# Schematic.net
KiCad netlist of a schematic drawn in Altium Designer
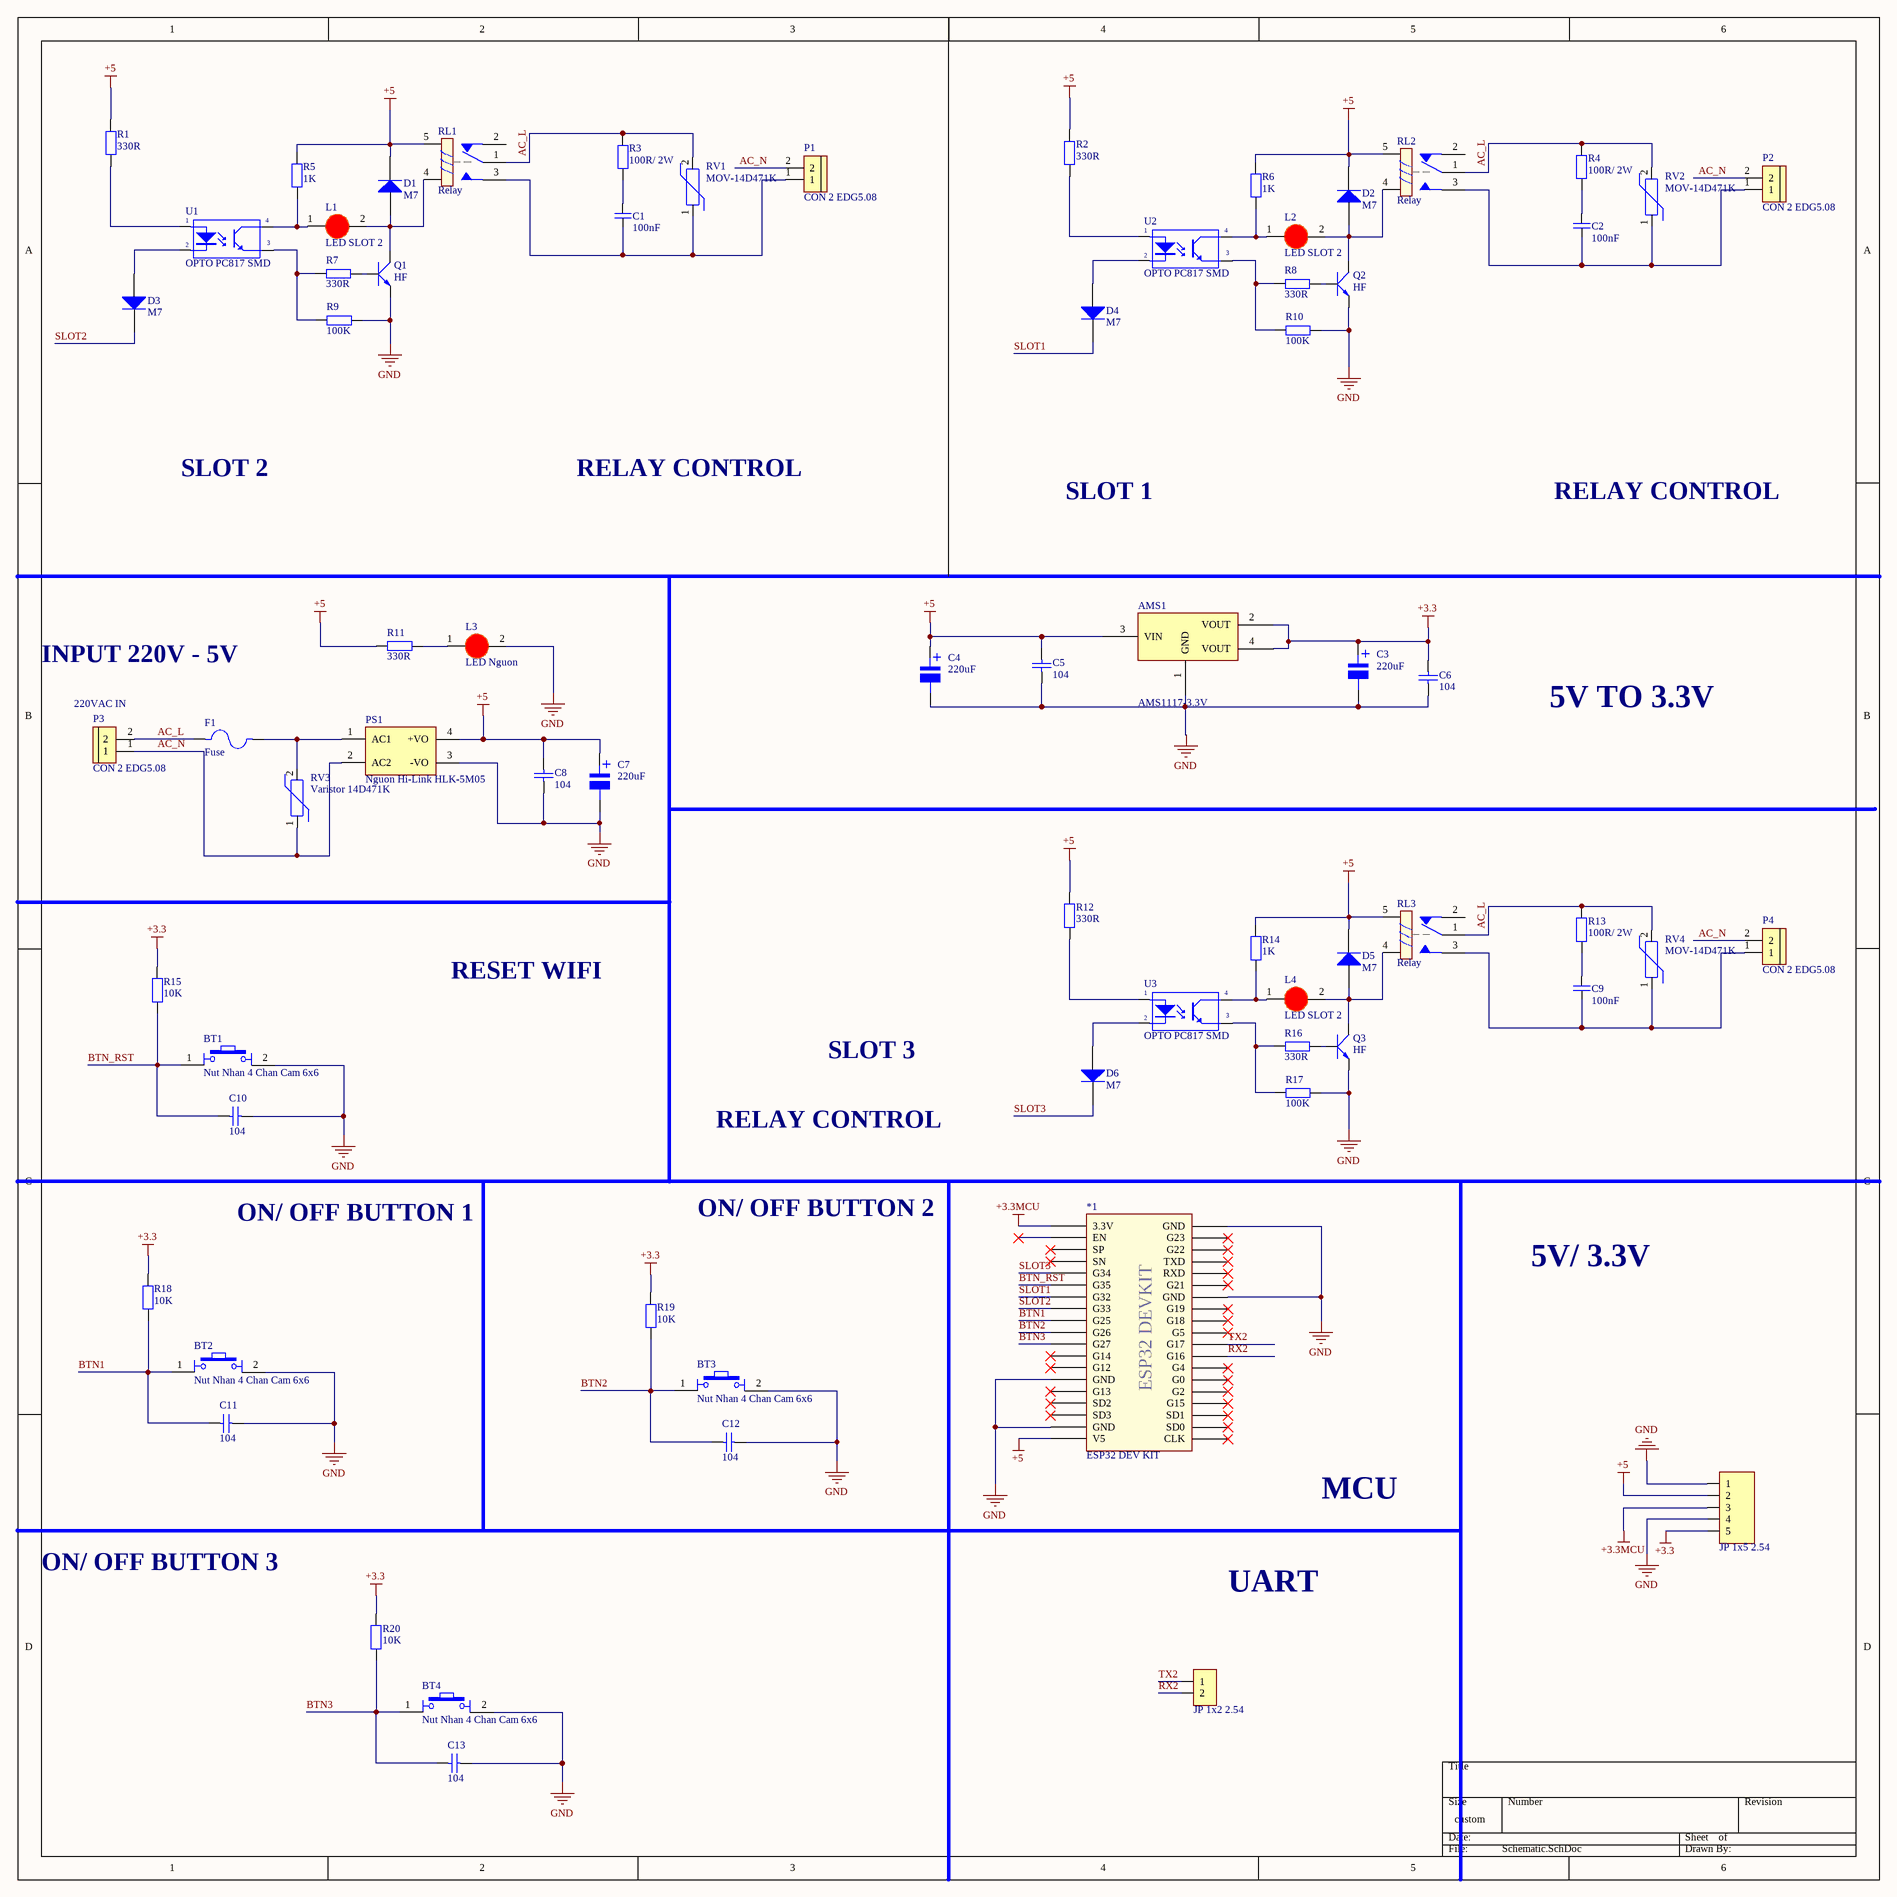
[diagram p0: Schematic.SchDoc]

(export (version "E")
  (design (tool "Eeschema 10.0.6"))
  (components
    (comp (ref "*1")
      (value "ESP32 DEV KIT")
      (footprint "ESP32 DEVKIT")
      (libsource (lib "Altium_Lib_by_KhueNguyenCreator") (part "ESP32 DEV KIT"))
    )
    (comp (ref "AMS1")
      (value "AMS1117-3.3V")
      (footprint "SOT223")
      (description "Dán")
      (libsource (lib "Altium_Lib_by_KhueNguyenCreator") (part "AMS1117 SMD"))
    )
    (comp (ref "BT1")
      (value "Nut Nhan 4 Chan Cam 6x6")
      (footprint "Nut Nhan 4 Chan Cam 6x6")
      (description "Nut Nhan 4 Chan 6x6mm")
      (libsource (lib "Altium_Lib_by_KhueNguyenCreator") (part "Nut Nhan 4 Chan Cam 6x6"))
    )
    (comp (ref "BT2")
      (value "Nut Nhan 4 Chan Cam 6x6")
      (footprint "Nut Nhan 4 Chan Cam 6x6")
      (description "Nut Nhan 4 Chan 6x6mm")
      (libsource (lib "Altium_Lib_by_KhueNguyenCreator") (part "Nut Nhan 4 Chan Cam 6x6"))
    )
    (comp (ref "BT3")
      (value "Nut Nhan 4 Chan Cam 6x6")
      (footprint "Nut Nhan 4 Chan Cam 6x6")
      (description "Nut Nhan 4 Chan 6x6mm")
      (libsource (lib "Altium_Lib_by_KhueNguyenCreator") (part "Nut Nhan 4 Chan Cam 6x6"))
    )
    (comp (ref "BT4")
      (value "Nut Nhan 4 Chan Cam 6x6")
      (footprint "Nut Nhan 4 Chan Cam 6x6")
      (description "Nut Nhan 4 Chan 6x6mm")
      (libsource (lib "Altium_Lib_by_KhueNguyenCreator") (part "Nut Nhan 4 Chan Cam 6x6"))
    )
    (comp (ref "C1")
      (value "100nF")
      (footprint "Cap_Poly_684J400V")
      (libsource (lib "Electronic4u") (part "Cap_Non-Polar"))
    )
    (comp (ref "C2")
      (value "100nF")
      (footprint "Cap_Poly_684J400V")
      (libsource (lib "Electronic4u") (part "Cap_Non-Polar"))
    )
    (comp (ref "C3")
      (value "220uF")
      (footprint "tu nhom 6.3 (d)")
      (description "Dán")
      (libsource (lib "Altium_Lib_by_KhueNguyenCreator") (part "Tu Nhom 220uF 16V"))
    )
    (comp (ref "C4")
      (value "220uF")
      (footprint "tu nhom 6.3 (d)")
      (description "Dán")
      (libsource (lib "Altium_Lib_by_KhueNguyenCreator") (part "Tu Nhom 220uF 16V"))
    )
    (comp (ref "C5")
      (value "104")
      (footprint "tu 0805")
      (description "Dán")
      (libsource (lib "Altium_Lib_by_KhueNguyenCreator") (part "Tu 0805 104 50V 10%"))
    )
    (comp (ref "C6")
      (value "104")
      (footprint "tu 0805")
      (description "Dán")
      (libsource (lib "Altium_Lib_by_KhueNguyenCreator") (part "Tu 0805 104 50V 10%"))
    )
    (comp (ref "C7")
      (value "220uF")
      (footprint "tu nhom 6.3 (d)")
      (description "Dán")
      (libsource (lib "Altium_Lib_by_KhueNguyenCreator") (part "Tu Nhom 220uF 16V"))
    )
    (comp (ref "C8")
      (value "104")
      (footprint "tu 0805")
      (description "Dán")
      (libsource (lib "Altium_Lib_by_KhueNguyenCreator") (part "Tu 0805 104 50V 10%"))
    )
    (comp (ref "C9")
      (value "100nF")
      (footprint "Cap_Poly_684J400V")
      (libsource (lib "Electronic4u") (part "Cap_Non-Polar"))
    )
    (comp (ref "C10")
      (value "104")
      (footprint "tu 0805")
      (description "Dán")
      (libsource (lib "Altium_Lib_by_KhueNguyenCreator") (part "Tu 0805 104 50V 10%"))
    )
    (comp (ref "C11")
      (value "104")
      (footprint "tu 0805")
      (description "Dán")
      (libsource (lib "Altium_Lib_by_KhueNguyenCreator") (part "Tu 0805 104 50V 10%"))
    )
    (comp (ref "C12")
      (value "104")
      (footprint "tu 0805")
      (description "Dán")
      (libsource (lib "Altium_Lib_by_KhueNguyenCreator") (part "Tu 0805 104 50V 10%"))
    )
    (comp (ref "C13")
      (value "104")
      (footprint "tu 0805")
      (description "Dán")
      (libsource (lib "Altium_Lib_by_KhueNguyenCreator") (part "Tu 0805 104 50V 10%"))
    )
    (comp (ref "D1")
      (value "M7")
      (footprint "DIODE SMA")
      (description "Dán")
      (libsource (lib "Altium_Lib_by_KhueNguyenCreator") (part "Diode M7 ( 4007 )"))
    )
    (comp (ref "D2")
      (value "M7")
      (footprint "DIODE SMA")
      (description "Dán")
      (libsource (lib "Altium_Lib_by_KhueNguyenCreator") (part "Diode M7 ( 4007 )"))
    )
    (comp (ref "D3")
      (value "M7")
      (footprint "DIODE SMA")
      (description "Dán")
      (libsource (lib "Altium_Lib_by_KhueNguyenCreator") (part "Diode M7 ( 4007 )"))
    )
    (comp (ref "D4")
      (value "M7")
      (footprint "DIODE SMA")
      (description "Dán")
      (libsource (lib "Altium_Lib_by_KhueNguyenCreator") (part "Diode M7 ( 4007 )"))
    )
    (comp (ref "D5")
      (value "M7")
      (footprint "DIODE SMA")
      (description "Dán")
      (libsource (lib "Altium_Lib_by_KhueNguyenCreator") (part "Diode M7 ( 4007 )"))
    )
    (comp (ref "D6")
      (value "M7")
      (footprint "DIODE SMA")
      (description "Dán")
      (libsource (lib "Altium_Lib_by_KhueNguyenCreator") (part "Diode M7 ( 4007 )"))
    )
    (comp (ref "F1")
      (value "Fuse")
      (footprint "FUSE")
      (description "Fuse, TE5 369 Series, Through Hole, Slow Blow, 300VAC, 1A, Radial ¦ Littelfuse 36911000000")
      (fields (field (name "MF") "Littelfuse") (field (name "MP") "36911000000"))
      (libsource (lib "Altium_Lib_by_KhueNguyenCreator") (part "Fuse"))
    )
    (comp (ref "JP1")
      (value "JP 1x5 2.54")
      (footprint "JP 1x5 DT")
      (description "Cắm")
      (libsource (lib "Altium_Lib_by_KhueNguyenCreator") (part "JP 1x5 2.54 Duc Thang"))
    )
    (comp (ref "JP2")
      (value "JP 1x2 2.54")
      (footprint "JP 1x2 DT")
      (description "Cắm")
      (libsource (lib "Altium_Lib_by_KhueNguyenCreator") (part "JP 1x2 2.54 Duc Thang"))
    )
    (comp (ref "L1")
      (value "LED SLOT 2")
      (footprint "LED-5MM-RED")
      (description "Cắm")
      (libsource (lib "Altium_Lib_by_KhueNguyenCreator") (part "LED 5mm Do"))
    )
    (comp (ref "L2")
      (value "LED SLOT 2")
      (footprint "LED-5MM-RED")
      (description "Cắm")
      (libsource (lib "Altium_Lib_by_KhueNguyenCreator") (part "LED 5mm Do"))
    )
    (comp (ref "L3")
      (value "LED Nguon")
      (footprint "LED-5MM-RED")
      (description "Cắm")
      (libsource (lib "Altium_Lib_by_KhueNguyenCreator") (part "LED 5mm Do"))
    )
    (comp (ref "L4")
      (value "LED SLOT 2")
      (footprint "LED-5MM-RED")
      (description "Cắm")
      (libsource (lib "Altium_Lib_by_KhueNguyenCreator") (part "LED 5mm Do"))
    )
    (comp (ref "P1")
      (value "CON 2 EDG5.08")
      (footprint "CON 2 2EDG5.08")
      (description "Cắm")
      (libsource (lib "Altium_Lib_by_KhueNguyenCreator") (part "CON 2 EDG5.08"))
    )
    (comp (ref "P2")
      (value "CON 2 EDG5.08")
      (footprint "CON 2 2EDG5.08")
      (description "Cắm")
      (libsource (lib "Altium_Lib_by_KhueNguyenCreator") (part "CON 2 EDG5.08"))
    )
    (comp (ref "P3")
      (value "CON 2 EDG5.08")
      (footprint "CON 2 2EDG5.08")
      (description "Cắm")
      (libsource (lib "") (part "CON 2 EDG5.08_1"))
    )
    (comp (ref "P4")
      (value "CON 2 EDG5.08")
      (footprint "CON 2 2EDG5.08")
      (description "Cắm")
      (libsource (lib "Altium_Lib_by_KhueNguyenCreator") (part "CON 2 EDG5.08"))
    )
    (comp (ref "PS1")
      (value "Nguon Hi-Link HLK-5M05")
      (footprint "Nguon HI-LINK 5M05")
      (description "AC DC 220V to 5V 5W 5Watt Isolated Switching Step-Down Power Supply Module Converter")
      (fields (field (name "MF") "Hi-link") (field (name "MP") "HLK-5M05"))
      (libsource (lib "Altium_Lib_by_KhueNguyenCreator") (part "Nguon Hi-Link HLK-5M05"))
    )
    (comp (ref "Q1")
      (value "HF")
      (footprint "SOT-23")
      (description "SOT-23")
      (libsource (lib "Altium_Lib_by_KhueNguyenCreator") (part "Trans C1815 HF SMD"))
    )
    (comp (ref "Q2")
      (value "HF")
      (footprint "SOT-23")
      (description "SOT-23")
      (libsource (lib "Altium_Lib_by_KhueNguyenCreator") (part "Trans C1815 HF SMD"))
    )
    (comp (ref "Q3")
      (value "HF")
      (footprint "SOT-23")
      (description "SOT-23")
      (libsource (lib "Altium_Lib_by_KhueNguyenCreator") (part "Trans C1815 HF SMD"))
    )
    (comp (ref "R1")
      (value "330R")
      (footprint "Tro SMD 0805")
      (description "Dán")
      (libsource (lib "Altium_Lib_by_KhueNguyenCreator") (part "Tro 0805 5% 330R"))
    )
    (comp (ref "R2")
      (value "330R")
      (footprint "Tro SMD 0805")
      (description "Dán")
      (libsource (lib "Altium_Lib_by_KhueNguyenCreator") (part "Tro 0805 5% 330R"))
    )
    (comp (ref "R3")
      (value "100R/ 2W")
      (footprint "tro vach 2w")
      (description "Cắm")
      (libsource (lib "Altium_Lib_by_KhueNguyenCreator") (part "Tro Vach 2W 5% 100R"))
    )
    (comp (ref "R4")
      (value "100R/ 2W")
      (footprint "tro vach 2w")
      (description "Cắm")
      (libsource (lib "Altium_Lib_by_KhueNguyenCreator") (part "Tro Vach 2W 5% 100R"))
    )
    (comp (ref "R5")
      (value "1K")
      (footprint "Tro SMD 0805")
      (description "Dán")
      (libsource (lib "Altium_Lib_by_KhueNguyenCreator") (part "Tro 0805 5% 330R"))
    )
    (comp (ref "R6")
      (value "1K")
      (footprint "Tro SMD 0805")
      (description "Dán")
      (libsource (lib "Altium_Lib_by_KhueNguyenCreator") (part "Tro 0805 5% 330R"))
    )
    (comp (ref "R7")
      (value "330R")
      (footprint "Tro SMD 0805")
      (description "Dán")
      (libsource (lib "Altium_Lib_by_KhueNguyenCreator") (part "Tro 0805 5% 330R"))
    )
    (comp (ref "R8")
      (value "330R")
      (footprint "Tro SMD 0805")
      (description "Dán")
      (libsource (lib "Altium_Lib_by_KhueNguyenCreator") (part "Tro 0805 5% 330R"))
    )
    (comp (ref "R9")
      (value "100K")
      (footprint "Tro SMD 0805")
      (description "Dán")
      (libsource (lib "Altium_Lib_by_KhueNguyenCreator") (part "Tro 0805 5% 330R"))
    )
    (comp (ref "R10")
      (value "100K")
      (footprint "Tro SMD 0805")
      (description "Dán")
      (libsource (lib "Altium_Lib_by_KhueNguyenCreator") (part "Tro 0805 5% 330R"))
    )
    (comp (ref "R11")
      (value "330R")
      (footprint "Tro SMD 0805")
      (description "Dán")
      (libsource (lib "Altium_Lib_by_KhueNguyenCreator") (part "Tro 0805 5% 330R"))
    )
    (comp (ref "R12")
      (value "330R")
      (footprint "Tro SMD 0805")
      (description "Dán")
      (libsource (lib "Altium_Lib_by_KhueNguyenCreator") (part "Tro 0805 5% 330R"))
    )
    (comp (ref "R13")
      (value "100R/ 2W")
      (footprint "tro vach 2w")
      (description "Cắm")
      (libsource (lib "Altium_Lib_by_KhueNguyenCreator") (part "Tro Vach 2W 5% 100R"))
    )
    (comp (ref "R14")
      (value "1K")
      (footprint "Tro SMD 0805")
      (description "Dán")
      (libsource (lib "Altium_Lib_by_KhueNguyenCreator") (part "Tro 0805 5% 330R"))
    )
    (comp (ref "R15")
      (value "10K")
      (footprint "Tro SMD 0805")
      (description "Dán")
      (libsource (lib "Altium_Lib_by_KhueNguyenCreator") (part "Tro 0805 5% 330R"))
    )
    (comp (ref "R16")
      (value "330R")
      (footprint "Tro SMD 0805")
      (description "Dán")
      (libsource (lib "Altium_Lib_by_KhueNguyenCreator") (part "Tro 0805 5% 330R"))
    )
    (comp (ref "R17")
      (value "100K")
      (footprint "Tro SMD 0805")
      (description "Dán")
      (libsource (lib "Altium_Lib_by_KhueNguyenCreator") (part "Tro 0805 5% 330R"))
    )
    (comp (ref "R18")
      (value "10K")
      (footprint "Tro SMD 0805")
      (description "Dán")
      (libsource (lib "Altium_Lib_by_KhueNguyenCreator") (part "Tro 0805 5% 330R"))
    )
    (comp (ref "R19")
      (value "10K")
      (footprint "Tro SMD 0805")
      (description "Dán")
      (libsource (lib "Altium_Lib_by_KhueNguyenCreator") (part "Tro 0805 5% 330R"))
    )
    (comp (ref "R20")
      (value "10K")
      (footprint "Tro SMD 0805")
      (description "Dán")
      (libsource (lib "Altium_Lib_by_KhueNguyenCreator") (part "Tro 0805 5% 330R"))
    )
    (comp (ref "RL1")
      (value "Relay")
      (footprint "Relay 5 Chan SRD")
      (description "Relay 5 Chan")
      (libsource (lib "Altium_Lib_by_KhueNguyenCreator") (part "Relay 5 Chan SRD"))
    )
    (comp (ref "RL2")
      (value "Relay")
      (footprint "Relay 5 Chan SRD")
      (description "Relay 5 Chan")
      (libsource (lib "Altium_Lib_by_KhueNguyenCreator") (part "Relay 5 Chan SRD"))
    )
    (comp (ref "RL3")
      (value "Relay")
      (footprint "Relay 5 Chan SRD")
      (description "Relay 5 Chan")
      (libsource (lib "Altium_Lib_by_KhueNguyenCreator") (part "Relay 5 Chan SRD"))
    )
    (comp (ref "RV1")
      (value "MOV-14D471K")
      (footprint "MOV14D471K")
      (description "470 V 4.5 kA Varistor 1 Circuit Through Hole Disc 14mm")
      (fields (field (name "MF") "Bourns"))
      (libsource (lib "Altium_Lib_by_KhueNguyenCreator") (part "MOV-14D471K"))
    )
    (comp (ref "RV2")
      (value "MOV-14D471K")
      (footprint "MOV14D471K")
      (description "470 V 4.5 kA Varistor 1 Circuit Through Hole Disc 14mm")
      (fields (field (name "MF") "Bourns"))
      (libsource (lib "Altium_Lib_by_KhueNguyenCreator") (part "MOV-14D471K"))
    )
    (comp (ref "RV3")
      (value "Varistor 14D471K")
      (footprint "MOV14D471K")
      (description "470 V 4.5 kA Varistor 1 Circuit Through Hole Disc 14mm")
      (fields (field (name "MP") "MOV-14D471K") (field (name "MF") "Bourns"))
      (libsource (lib "MOV-14D471K") (part "MOV-14D471K"))
    )
    (comp (ref "RV4")
      (value "MOV-14D471K")
      (footprint "MOV14D471K")
      (description "470 V 4.5 kA Varistor 1 Circuit Through Hole Disc 14mm")
      (fields (field (name "MF") "Bourns"))
      (libsource (lib "Altium_Lib_by_KhueNguyenCreator") (part "MOV-14D471K"))
    )
    (comp (ref "U1")
      (value "OPTO PC817 SMD")
      (footprint "SOP4")
      (description "Single Opto")
      (libsource (lib "Altium_Lib_by_KhueNguyenCreator") (part "OPTO PC817 SMD"))
    )
    (comp (ref "U2")
      (value "OPTO PC817 SMD")
      (footprint "SOP4")
      (description "Single Opto")
      (libsource (lib "Altium_Lib_by_KhueNguyenCreator") (part "OPTO PC817 SMD"))
    )
    (comp (ref "U3")
      (value "OPTO PC817 SMD")
      (footprint "SOP4")
      (description "Single Opto")
      (libsource (lib "Altium_Lib_by_KhueNguyenCreator") (part "OPTO PC817 SMD"))
    )
  )
  (nets
    (net (code "1") (name "+3.3") (class "Default")
      (node (ref "AMS1") (pin "2") (pinfunction "VOUT_2") (pintype "passive"))
      (node (ref "AMS1") (pin "4") (pinfunction "VOUT_4") (pintype "passive"))
      (node (ref "C3") (pin "1") (pinfunction "1_1") (pintype "passive"))
      (node (ref "C6") (pin "1") (pinfunction "1_1") (pintype "passive"))
      (node (ref "JP1") (pin "5") (pinfunction "5_5") (pintype "passive"))
      (node (ref "R15") (pin "1") (pinfunction "1_1") (pintype "passive"))
      (node (ref "R18") (pin "1") (pinfunction "1_1") (pintype "passive"))
      (node (ref "R19") (pin "1") (pinfunction "1_1") (pintype "passive"))
      (node (ref "R20") (pin "1") (pinfunction "1_1") (pintype "passive"))
    )
    (net (code "2") (name "+3.3MCU") (class "Default")
      (node (ref "*1") (pin "1") (pinfunction "3.3V_1") (pintype "passive"))
      (node (ref "JP1") (pin "3") (pinfunction "3_3") (pintype "passive"))
    )
    (net (code "3") (name "+5") (class "Default")
      (node (ref "*1") (pin "19") (pinfunction "V5_19") (pintype "passive"))
      (node (ref "AMS1") (pin "3") (pinfunction "VIN_3") (pintype "passive"))
      (node (ref "C4") (pin "1") (pinfunction "1_1") (pintype "passive"))
      (node (ref "C5") (pin "1") (pinfunction "1_1") (pintype "passive"))
      (node (ref "C7") (pin "1") (pinfunction "1_1") (pintype "passive"))
      (node (ref "C8") (pin "1") (pinfunction "1_1") (pintype "passive"))
      (node (ref "D1") (pin "2") (pinfunction "K_2") (pintype "passive"))
      (node (ref "D2") (pin "2") (pinfunction "K_2") (pintype "passive"))
      (node (ref "D5") (pin "2") (pinfunction "K_2") (pintype "passive"))
      (node (ref "JP1") (pin "2") (pinfunction "2_2") (pintype "passive"))
      (node (ref "PS1") (pin "4") (pinfunction "+VO_4") (pintype "passive"))
      (node (ref "R1") (pin "2") (pinfunction "2_2") (pintype "passive"))
      (node (ref "R11") (pin "2") (pinfunction "2_2") (pintype "passive"))
      (node (ref "R12") (pin "2") (pinfunction "2_2") (pintype "passive"))
      (node (ref "R14") (pin "2") (pinfunction "2_2") (pintype "passive"))
      (node (ref "R2") (pin "2") (pinfunction "2_2") (pintype "passive"))
      (node (ref "R5") (pin "2") (pinfunction "2_2") (pintype "passive"))
      (node (ref "R6") (pin "2") (pinfunction "2_2") (pintype "passive"))
      (node (ref "RL1") (pin "5") (pinfunction "5_5") (pintype "passive"))
      (node (ref "RL2") (pin "5") (pinfunction "5_5") (pintype "passive"))
      (node (ref "RL3") (pin "5") (pinfunction "5_5") (pintype "passive"))
    )
    (net (code "4") (name "/AC_L") (class "Default")
      (node (ref "F1") (pin "1") (pinfunction "1_1") (pintype "passive"))
      (node (ref "P3") (pin "2") (pinfunction "2_2") (pintype "passive"))
      (node (ref "R13") (pin "2") (pinfunction "2_2") (pintype "passive"))
      (node (ref "R3") (pin "2") (pinfunction "2_2") (pintype "passive"))
      (node (ref "R4") (pin "2") (pinfunction "2_2") (pintype "passive"))
      (node (ref "RL1") (pin "1") (pinfunction "1_1") (pintype "passive"))
      (node (ref "RL2") (pin "1") (pinfunction "1_1") (pintype "passive"))
      (node (ref "RL3") (pin "1") (pinfunction "1_1") (pintype "passive"))
      (node (ref "RV1") (pin "2") (pinfunction "2_2") (pintype "bidirectional"))
      (node (ref "RV2") (pin "2") (pinfunction "2_2") (pintype "bidirectional"))
      (node (ref "RV4") (pin "2") (pinfunction "2_2") (pintype "bidirectional"))
    )
    (net (code "5") (name "/AC_N") (class "Default")
      (node (ref "P1") (pin "2") (pinfunction "2_2") (pintype "passive"))
      (node (ref "P2") (pin "2") (pinfunction "2_2") (pintype "passive"))
      (node (ref "P3") (pin "1") (pinfunction "1_1") (pintype "passive"))
      (node (ref "P4") (pin "2") (pinfunction "2_2") (pintype "passive"))
      (node (ref "PS1") (pin "2") (pinfunction "AC2_2") (pintype "passive"))
      (node (ref "RV3") (pin "1") (pinfunction "1_1") (pintype "bidirectional"))
    )
    (net (code "6") (name "/BTN1") (class "Default")
      (node (ref "*1") (pin "9") (pinfunction "G25_9") (pintype "passive"))
      (node (ref "BT2") (pin "1") (pintype "passive"))
      (node (ref "C11") (pin "1") (pinfunction "1_1") (pintype "passive"))
      (node (ref "R18") (pin "2") (pinfunction "2_2") (pintype "passive"))
    )
    (net (code "7") (name "/BTN2") (class "Default")
      (node (ref "*1") (pin "10") (pinfunction "G26_10") (pintype "passive"))
      (node (ref "BT3") (pin "1") (pintype "passive"))
      (node (ref "C12") (pin "1") (pinfunction "1_1") (pintype "passive"))
      (node (ref "R19") (pin "2") (pinfunction "2_2") (pintype "passive"))
    )
    (net (code "8") (name "/BTN3") (class "Default")
      (node (ref "*1") (pin "11") (pinfunction "G27_11") (pintype "passive"))
      (node (ref "BT4") (pin "1") (pintype "passive"))
      (node (ref "C13") (pin "1") (pinfunction "1_1") (pintype "passive"))
      (node (ref "R20") (pin "2") (pinfunction "2_2") (pintype "passive"))
    )
    (net (code "9") (name "/BTN_RST") (class "Default")
      (node (ref "*1") (pin "6") (pinfunction "G35_6") (pintype "passive"))
      (node (ref "BT1") (pin "1") (pintype "passive"))
      (node (ref "C10") (pin "1") (pinfunction "1_1") (pintype "passive"))
      (node (ref "R15") (pin "2") (pinfunction "2_2") (pintype "passive"))
    )
    (net (code "10") (name "/RX2") (class "Default")
      (node (ref "*1") (pin "27") (pinfunction "G16_27") (pintype "passive"))
      (node (ref "JP2") (pin "2") (pinfunction "2_2") (pintype "passive"))
    )
    (net (code "11") (name "/SLOT1") (class "Default")
      (node (ref "*1") (pin "7") (pinfunction "G32_7") (pintype "passive"))
      (node (ref "D4") (pin "2") (pinfunction "K_2") (pintype "passive"))
    )
    (net (code "12") (name "/SLOT2") (class "Default")
      (node (ref "*1") (pin "8") (pinfunction "G33_8") (pintype "passive"))
      (node (ref "D3") (pin "2") (pinfunction "K_2") (pintype "passive"))
    )
    (net (code "13") (name "/SLOT3") (class "Default")
      (node (ref "*1") (pin "5") (pinfunction "G34_5") (pintype "passive"))
      (node (ref "D6") (pin "2") (pinfunction "K_2") (pintype "passive"))
    )
    (net (code "14") (name "/TX2") (class "Default")
      (node (ref "*1") (pin "28") (pinfunction "G17_28") (pintype "passive"))
      (node (ref "JP2") (pin "1") (pinfunction "1_1") (pintype "passive"))
    )
    (net (code "15") (name "GND") (class "Default")
      (node (ref "*1") (pin "14") (pinfunction "GND_14") (pintype "passive"))
      (node (ref "*1") (pin "18") (pinfunction "GND_18") (pintype "passive"))
      (node (ref "*1") (pin "32") (pinfunction "GND_32") (pintype "passive"))
      (node (ref "*1") (pin "38") (pinfunction "GND_38") (pintype "passive"))
      (node (ref "AMS1") (pin "1") (pinfunction "GND_1") (pintype "passive"))
      (node (ref "BT1") (pin "2") (pintype "passive"))
      (node (ref "BT2") (pin "2") (pintype "passive"))
      (node (ref "BT3") (pin "2") (pintype "passive"))
      (node (ref "BT4") (pin "2") (pintype "passive"))
      (node (ref "C10") (pin "2") (pinfunction "2_2") (pintype "passive"))
      (node (ref "C11") (pin "2") (pinfunction "2_2") (pintype "passive"))
      (node (ref "C12") (pin "2") (pinfunction "2_2") (pintype "passive"))
      (node (ref "C13") (pin "2") (pinfunction "2_2") (pintype "passive"))
      (node (ref "C3") (pin "2") (pinfunction "2_2") (pintype "passive"))
      (node (ref "C4") (pin "2") (pinfunction "2_2") (pintype "passive"))
      (node (ref "C5") (pin "2") (pinfunction "2_2") (pintype "passive"))
      (node (ref "C6") (pin "2") (pinfunction "2_2") (pintype "passive"))
      (node (ref "C7") (pin "2") (pinfunction "2_2") (pintype "passive"))
      (node (ref "C8") (pin "2") (pinfunction "2_2") (pintype "passive"))
      (node (ref "JP1") (pin "1") (pinfunction "1_1") (pintype "passive"))
      (node (ref "JP1") (pin "4") (pinfunction "4_4") (pintype "passive"))
      (node (ref "L3") (pin "2") (pinfunction "K_2") (pintype "passive"))
      (node (ref "PS1") (pin "3") (pinfunction "-VO_3") (pintype "passive"))
      (node (ref "Q1") (pin "2") (pinfunction "E_2") (pintype "passive"))
      (node (ref "Q2") (pin "2") (pinfunction "E_2") (pintype "passive"))
      (node (ref "Q3") (pin "2") (pinfunction "E_2") (pintype "passive"))
      (node (ref "R10") (pin "1") (pinfunction "1_1") (pintype "passive"))
      (node (ref "R17") (pin "1") (pinfunction "1_1") (pintype "passive"))
      (node (ref "R9") (pin "1") (pinfunction "1_1") (pintype "passive"))
    )
    (net (code "16") (name "Net-(C1-Pad1)") (class "Default")
      (node (ref "C1") (pin "1") (pinfunction "1_1") (pintype "passive"))
      (node (ref "P1") (pin "1") (pinfunction "1_1") (pintype "passive"))
      (node (ref "RL1") (pin "3") (pinfunction "3_3") (pintype "passive"))
      (node (ref "RV1") (pin "1") (pinfunction "1_1") (pintype "bidirectional"))
    )
    (net (code "17") (name "Net-(C1-Pad2)") (class "Default")
      (node (ref "C1") (pin "2") (pinfunction "2_2") (pintype "passive"))
      (node (ref "R3") (pin "1") (pinfunction "1_1") (pintype "passive"))
    )
    (net (code "18") (name "Net-(C2-Pad1)") (class "Default")
      (node (ref "C2") (pin "1") (pinfunction "1_1") (pintype "passive"))
      (node (ref "P2") (pin "1") (pinfunction "1_1") (pintype "passive"))
      (node (ref "RL2") (pin "3") (pinfunction "3_3") (pintype "passive"))
      (node (ref "RV2") (pin "1") (pinfunction "1_1") (pintype "bidirectional"))
    )
    (net (code "19") (name "Net-(C2-Pad2)") (class "Default")
      (node (ref "C2") (pin "2") (pinfunction "2_2") (pintype "passive"))
      (node (ref "R4") (pin "1") (pinfunction "1_1") (pintype "passive"))
    )
    (net (code "20") (name "Net-(C9-Pad1)") (class "Default")
      (node (ref "C9") (pin "1") (pinfunction "1_1") (pintype "passive"))
      (node (ref "P4") (pin "1") (pinfunction "1_1") (pintype "passive"))
      (node (ref "RL3") (pin "3") (pinfunction "3_3") (pintype "passive"))
      (node (ref "RV4") (pin "1") (pinfunction "1_1") (pintype "bidirectional"))
    )
    (net (code "21") (name "Net-(C9-Pad2)") (class "Default")
      (node (ref "C9") (pin "2") (pinfunction "2_2") (pintype "passive"))
      (node (ref "R13") (pin "1") (pinfunction "1_1") (pintype "passive"))
    )
    (net (code "22") (name "Net-(D1-A)") (class "Default")
      (node (ref "D1") (pin "1") (pinfunction "A_1") (pintype "passive"))
      (node (ref "L1") (pin "2") (pinfunction "K_2") (pintype "passive"))
      (node (ref "Q1") (pin "3") (pinfunction "C_3") (pintype "passive"))
      (node (ref "RL1") (pin "4") (pinfunction "4_4") (pintype "passive"))
    )
    (net (code "23") (name "Net-(D2-A)") (class "Default")
      (node (ref "D2") (pin "1") (pinfunction "A_1") (pintype "passive"))
      (node (ref "L2") (pin "2") (pinfunction "K_2") (pintype "passive"))
      (node (ref "Q2") (pin "3") (pinfunction "C_3") (pintype "passive"))
      (node (ref "RL2") (pin "4") (pinfunction "4_4") (pintype "passive"))
    )
    (net (code "24") (name "Net-(D3-A)") (class "Default")
      (node (ref "D3") (pin "1") (pinfunction "A_1") (pintype "passive"))
      (node (ref "U1") (pin "2") (pinfunction "K_2") (pintype "passive"))
    )
    (net (code "25") (name "Net-(D4-A)") (class "Default")
      (node (ref "D4") (pin "1") (pinfunction "A_1") (pintype "passive"))
      (node (ref "U2") (pin "2") (pinfunction "K_2") (pintype "passive"))
    )
    (net (code "26") (name "Net-(D5-A)") (class "Default")
      (node (ref "D5") (pin "1") (pinfunction "A_1") (pintype "passive"))
      (node (ref "L4") (pin "2") (pinfunction "K_2") (pintype "passive"))
      (node (ref "Q3") (pin "3") (pinfunction "C_3") (pintype "passive"))
      (node (ref "RL3") (pin "4") (pinfunction "4_4") (pintype "passive"))
    )
    (net (code "27") (name "Net-(D6-A)") (class "Default")
      (node (ref "D6") (pin "1") (pinfunction "A_1") (pintype "passive"))
      (node (ref "U3") (pin "2") (pinfunction "K_2") (pintype "passive"))
    )
    (net (code "28") (name "Net-(L1-A)") (class "Default")
      (node (ref "L1") (pin "1") (pinfunction "A_1") (pintype "passive"))
      (node (ref "R5") (pin "1") (pinfunction "1_1") (pintype "passive"))
      (node (ref "U1") (pin "4") (pinfunction "C_4") (pintype "passive"))
    )
    (net (code "29") (name "Net-(L2-A)") (class "Default")
      (node (ref "L2") (pin "1") (pinfunction "A_1") (pintype "passive"))
      (node (ref "R6") (pin "1") (pinfunction "1_1") (pintype "passive"))
      (node (ref "U2") (pin "4") (pinfunction "C_4") (pintype "passive"))
    )
    (net (code "30") (name "Net-(L3-A)") (class "Default")
      (node (ref "L3") (pin "1") (pinfunction "A_1") (pintype "passive"))
      (node (ref "R11") (pin "1") (pinfunction "1_1") (pintype "passive"))
    )
    (net (code "31") (name "Net-(L4-A)") (class "Default")
      (node (ref "L4") (pin "1") (pinfunction "A_1") (pintype "passive"))
      (node (ref "R14") (pin "1") (pinfunction "1_1") (pintype "passive"))
      (node (ref "U3") (pin "4") (pinfunction "C_4") (pintype "passive"))
    )
    (net (code "32") (name "Net-(PS1-AC1)") (class "Default")
      (node (ref "F1") (pin "2") (pinfunction "2_2") (pintype "passive"))
      (node (ref "PS1") (pin "1") (pinfunction "AC1_1") (pintype "passive"))
      (node (ref "RV3") (pin "2") (pinfunction "2_2") (pintype "bidirectional"))
    )
    (net (code "33") (name "Net-(Q1-B)") (class "Default")
      (node (ref "Q1") (pin "1") (pinfunction "B_1") (pintype "passive"))
      (node (ref "R7") (pin "1") (pinfunction "1_1") (pintype "passive"))
    )
    (net (code "34") (name "Net-(Q2-B)") (class "Default")
      (node (ref "Q2") (pin "1") (pinfunction "B_1") (pintype "passive"))
      (node (ref "R8") (pin "1") (pinfunction "1_1") (pintype "passive"))
    )
    (net (code "35") (name "Net-(Q3-B)") (class "Default")
      (node (ref "Q3") (pin "1") (pinfunction "B_1") (pintype "passive"))
      (node (ref "R16") (pin "1") (pinfunction "1_1") (pintype "passive"))
    )
    (net (code "36") (name "Net-(U1-A)") (class "Default")
      (node (ref "R1") (pin "1") (pinfunction "1_1") (pintype "passive"))
      (node (ref "U1") (pin "1") (pinfunction "A_1") (pintype "passive"))
    )
    (net (code "37") (name "Net-(U1-E)") (class "Default")
      (node (ref "R7") (pin "2") (pinfunction "2_2") (pintype "passive"))
      (node (ref "R9") (pin "2") (pinfunction "2_2") (pintype "passive"))
      (node (ref "U1") (pin "3") (pinfunction "E_3") (pintype "passive"))
    )
    (net (code "38") (name "Net-(U2-A)") (class "Default")
      (node (ref "R2") (pin "1") (pinfunction "1_1") (pintype "passive"))
      (node (ref "U2") (pin "1") (pinfunction "A_1") (pintype "passive"))
    )
    (net (code "39") (name "Net-(U2-E)") (class "Default")
      (node (ref "R10") (pin "2") (pinfunction "2_2") (pintype "passive"))
      (node (ref "R8") (pin "2") (pinfunction "2_2") (pintype "passive"))
      (node (ref "U2") (pin "3") (pinfunction "E_3") (pintype "passive"))
    )
    (net (code "40") (name "Net-(U3-A)") (class "Default")
      (node (ref "R12") (pin "1") (pinfunction "1_1") (pintype "passive"))
      (node (ref "U3") (pin "1") (pinfunction "A_1") (pintype "passive"))
    )
    (net (code "41") (name "Net-(U3-E)") (class "Default")
      (node (ref "R16") (pin "2") (pinfunction "2_2") (pintype "passive"))
      (node (ref "R17") (pin "2") (pinfunction "2_2") (pintype "passive"))
      (node (ref "U3") (pin "3") (pinfunction "E_3") (pintype "passive"))
    )
    (net (code "42") (name "unconnected-(*1-CLK-Pad20)") (class "Default")
      (node (ref "*1") (pin "20") (pinfunction "CLK_20") (pintype "passive+no_connect"))
    )
    (net (code "43") (name "unconnected-(*1-EN-Pad2)") (class "Default")
      (node (ref "*1") (pin "2") (pinfunction "EN_2") (pintype "passive+no_connect"))
    )
    (net (code "44") (name "unconnected-(*1-G0-Pad25)") (class "Default")
      (node (ref "*1") (pin "25") (pinfunction "G0_25") (pintype "passive+no_connect"))
    )
    (net (code "45") (name "unconnected-(*1-G2-Pad24)") (class "Default")
      (node (ref "*1") (pin "24") (pinfunction "G2_24") (pintype "passive+no_connect"))
    )
    (net (code "46") (name "unconnected-(*1-G4-Pad26)") (class "Default")
      (node (ref "*1") (pin "26") (pinfunction "G4_26") (pintype "passive+no_connect"))
    )
    (net (code "47") (name "unconnected-(*1-G5-Pad29)") (class "Default")
      (node (ref "*1") (pin "29") (pinfunction "G5_29") (pintype "passive+no_connect"))
    )
    (net (code "48") (name "unconnected-(*1-G12-Pad13)") (class "Default")
      (node (ref "*1") (pin "13") (pinfunction "G12_13") (pintype "passive+no_connect"))
    )
    (net (code "49") (name "unconnected-(*1-G13-Pad15)") (class "Default")
      (node (ref "*1") (pin "15") (pinfunction "G13_15") (pintype "passive+no_connect"))
    )
    (net (code "50") (name "unconnected-(*1-G14-Pad12)") (class "Default")
      (node (ref "*1") (pin "12") (pinfunction "G14_12") (pintype "passive+no_connect"))
    )
    (net (code "51") (name "unconnected-(*1-G15-Pad23)") (class "Default")
      (node (ref "*1") (pin "23") (pinfunction "G15_23") (pintype "passive+no_connect"))
    )
    (net (code "52") (name "unconnected-(*1-G18-Pad30)") (class "Default")
      (node (ref "*1") (pin "30") (pinfunction "G18_30") (pintype "passive+no_connect"))
    )
    (net (code "53") (name "unconnected-(*1-G19-Pad31)") (class "Default")
      (node (ref "*1") (pin "31") (pinfunction "G19_31") (pintype "passive+no_connect"))
    )
    (net (code "54") (name "unconnected-(*1-G21-Pad33)") (class "Default")
      (node (ref "*1") (pin "33") (pinfunction "G21_33") (pintype "passive+no_connect"))
    )
    (net (code "55") (name "unconnected-(*1-G22-Pad36)") (class "Default")
      (node (ref "*1") (pin "36") (pinfunction "G22_36") (pintype "passive+no_connect"))
    )
    (net (code "56") (name "unconnected-(*1-G23-Pad37)") (class "Default")
      (node (ref "*1") (pin "37") (pinfunction "G23_37") (pintype "passive+no_connect"))
    )
    (net (code "57") (name "unconnected-(*1-RXD-Pad34)") (class "Default")
      (node (ref "*1") (pin "34") (pinfunction "RXD_34") (pintype "passive+no_connect"))
    )
    (net (code "58") (name "unconnected-(*1-SD0-Pad21)") (class "Default")
      (node (ref "*1") (pin "21") (pinfunction "SD0_21") (pintype "passive+no_connect"))
    )
    (net (code "59") (name "unconnected-(*1-SD1-Pad22)") (class "Default")
      (node (ref "*1") (pin "22") (pinfunction "SD1_22") (pintype "passive+no_connect"))
    )
    (net (code "60") (name "unconnected-(*1-SD2-Pad16)") (class "Default")
      (node (ref "*1") (pin "16") (pinfunction "SD2_16") (pintype "passive+no_connect"))
    )
    (net (code "61") (name "unconnected-(*1-SD3-Pad17)") (class "Default")
      (node (ref "*1") (pin "17") (pinfunction "SD3_17") (pintype "passive+no_connect"))
    )
    (net (code "62") (name "unconnected-(*1-SN-Pad4)") (class "Default")
      (node (ref "*1") (pin "4") (pinfunction "SN_4") (pintype "passive+no_connect"))
    )
    (net (code "63") (name "unconnected-(*1-SP-Pad3)") (class "Default")
      (node (ref "*1") (pin "3") (pinfunction "SP_3") (pintype "passive+no_connect"))
    )
    (net (code "64") (name "unconnected-(*1-TXD-Pad35)") (class "Default")
      (node (ref "*1") (pin "35") (pinfunction "TXD_35") (pintype "passive+no_connect"))
    )
    (net (code "65") (name "unconnected-(RL1-Pad2)") (class "Default")
      (node (ref "RL1") (pin "2") (pinfunction "2_2") (pintype "passive"))
    )
    (net (code "66") (name "unconnected-(RL2-Pad2)") (class "Default")
      (node (ref "RL2") (pin "2") (pinfunction "2_2") (pintype "passive"))
    )
    (net (code "67") (name "unconnected-(RL3-Pad2)") (class "Default")
      (node (ref "RL3") (pin "2") (pinfunction "2_2") (pintype "passive"))
    )
  )
)
